# flasher.net
KiCad netlist of a schematic drawn in EAGLE
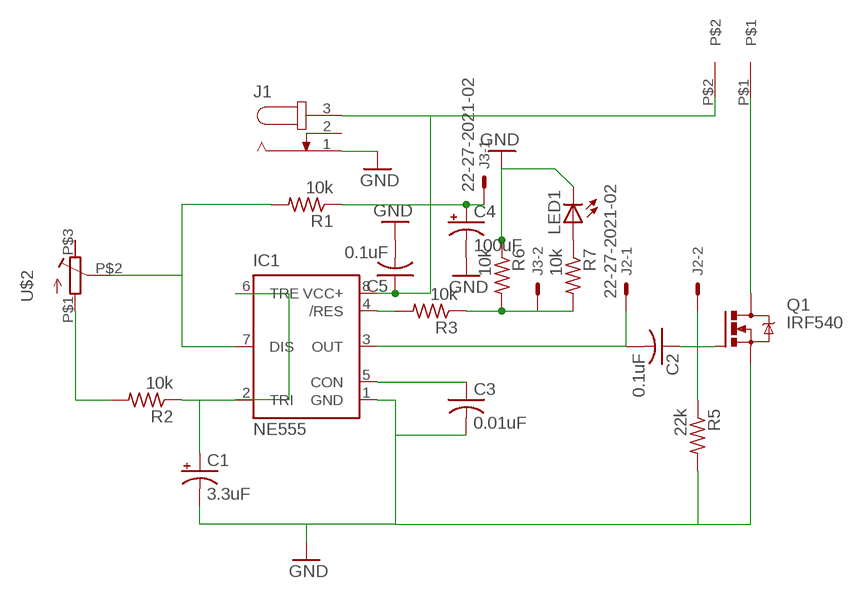
[diagram p0: schematic, sheet 1]

(export (version "E")
  (design (tool "Eeschema 10.0.6"))
  (components
    (comp (ref "C1")
      (value "3.3uF")
      (footprint "eagle-import:E2,5-5")
      (libsource (lib "eagle-import") (part "CPOL-USE2.5-5"))
    )
    (comp (ref "C2")
      (value "0.1uF")
      (footprint "eagle-import:C050-030X075")
      (libsource (lib "eagle-import") (part "C-US050-030X075"))
    )
    (comp (ref "C3")
      (value "0.01uF")
      (footprint "eagle-import:C025-025X050")
      (libsource (lib "eagle-import") (part "C-US025-025X050"))
    )
    (comp (ref "C4")
      (value "100uF")
      (footprint "eagle-import:E2,5-5")
      (libsource (lib "eagle-import") (part "CPOL-USE2.5-5"))
    )
    (comp (ref "C5")
      (value "0.1uF")
      (footprint "eagle-import:C025-025X050")
      (libsource (lib "eagle-import") (part "C-US025-025X050"))
    )
    (comp (ref "IC1")
      (value "NE555")
      (footprint "eagle-import:DIL-08")
      (fields (field (name "MF") "Arrow Electronics") (field (name "MPN") "NE555N"))
      (libsource (lib "eagle-import") (part "NE555"))
    )
    (comp (ref "J1")
      (value "JACK-PLUG0")
      (footprint "eagle-import:SPC4077")
      (libsource (lib "eagle-import") (part "JACK-PLUG0"))
    )
    (comp (ref "J2")
      (value "22-27-2021-02")
      (footprint "eagle-import:6410-02")
      (libsource (lib "eagle-import") (part "22-?-0227-2021"))
    )
    (comp (ref "J3")
      (value "22-27-2021-02")
      (footprint "eagle-import:6410-02")
      (libsource (lib "eagle-import") (part "22-?-0227-2021"))
    )
    (comp (ref "LED1")
      (value "LED5MM")
      (footprint "eagle-import:LED5MM")
      (libsource (lib "eagle-import") (part "LED5MM"))
    )
    (comp (ref "Q1")
      (value "IRF540")
      (footprint "eagle-import:TO220BV")
      (libsource (lib "eagle-import") (part "IRF540"))
    )
    (comp (ref "R1")
      (value "10k")
      (footprint "eagle-import:0207_10")
      (libsource (lib "eagle-import") (part "R-US_0207/10"))
    )
    (comp (ref "R2")
      (value "10k")
      (footprint "eagle-import:0207_10")
      (libsource (lib "eagle-import") (part "R-US_0207/10"))
    )
    (comp (ref "R3")
      (value "10k")
      (footprint "eagle-import:0207_10")
      (libsource (lib "eagle-import") (part "R-US_0207/10"))
    )
    (comp (ref "R5")
      (value "22k")
      (footprint "eagle-import:0207_10")
      (libsource (lib "eagle-import") (part "R-US_0207/10"))
    )
    (comp (ref "R6")
      (value "10k")
      (footprint "eagle-import:0207_10")
      (libsource (lib "eagle-import") (part "R-US_0207/10"))
    )
    (comp (ref "R7")
      (value "10k")
      (footprint "eagle-import:0207_10")
      (libsource (lib "eagle-import") (part "R-US_0207/10"))
    )
    (comp (ref "U$1")
      (value "DG301-5.0")
      (footprint "eagle-import:DG301-5.0")
      (libsource (lib "eagle-import") (part "DG301-5.0"))
    )
    (comp (ref "U$2")
      (value "PANELMOUNT_POT")
      (footprint "eagle-import:PANELMOUNT_POT")
      (libsource (lib "eagle-import") (part "PANELMOUNT_POT"))
    )
  )
  (nets
    (net (code "1") (name "GND") (class "Default")
      (node (ref "C1") (pin "-") (pinfunction "-_-") (pintype "passive"))
      (node (ref "C3") (pin "2") (pinfunction "2_2") (pintype "passive"))
      (node (ref "C4") (pin "-") (pinfunction "-_-") (pintype "passive"))
      (node (ref "C5") (pin "2") (pinfunction "2_2") (pintype "passive"))
      (node (ref "IC1") (pin "1") (pinfunction "GND_1") (pintype "power_in"))
      (node (ref "J1") (pin "1") (pinfunction "1_1") (pintype "passive"))
      (node (ref "LED1") (pin "K") (pinfunction "C_K") (pintype "passive"))
      (node (ref "Q1") (pin "S") (pinfunction "S_S") (pintype "passive"))
      (node (ref "R5") (pin "2") (pinfunction "2_2") (pintype "passive"))
      (node (ref "R6") (pin "1") (pinfunction "1_1") (pintype "passive"))
    )
    (net (code "2") (name "Net-(IC1-CON)") (class "Default")
      (node (ref "C3") (pin "1") (pinfunction "1_1") (pintype "passive"))
      (node (ref "IC1") (pin "5") (pinfunction "CON_5") (pintype "input"))
    )
    (net (code "3") (name "Net-(IC1-DIS)") (class "Default")
      (node (ref "IC1") (pin "7") (pinfunction "DIS_7") (pintype "input"))
      (node (ref "R1") (pin "2") (pinfunction "2_2") (pintype "passive"))
      (node (ref "U$2") (pin "P$2") (pinfunction "2_P$2") (pintype "passive"))
    )
    (net (code "4") (name "Net-(IC1-OUT)") (class "Default")
      (node (ref "C2") (pin "2") (pinfunction "2_2") (pintype "passive"))
      (node (ref "IC1") (pin "3") (pinfunction "OUT_3") (pintype "output"))
      (node (ref "J2") (pin "1") (pinfunction "S_1") (pintype "passive"))
    )
    (net (code "5") (name "Net-(IC1-TRE)") (class "Default")
      (node (ref "C1") (pin "+") (pinfunction "+_+") (pintype "passive"))
      (node (ref "IC1") (pin "2") (pinfunction "TRI_2") (pintype "input"))
      (node (ref "IC1") (pin "6") (pinfunction "TRE_6") (pintype "input"))
      (node (ref "R2") (pin "1") (pinfunction "1_1") (pintype "passive"))
    )
    (net (code "6") (name "Net-(IC1-VCC+)") (class "Default")
      (node (ref "C4") (pin "+") (pinfunction "+_+") (pintype "passive"))
      (node (ref "C5") (pin "1") (pinfunction "1_1") (pintype "passive"))
      (node (ref "IC1") (pin "8") (pinfunction "VCC+_8") (pintype "power_in"))
      (node (ref "J1") (pin "3") (pinfunction "3_3") (pintype "passive"))
      (node (ref "J3") (pin "1") (pinfunction "S_1") (pintype "passive"))
      (node (ref "R1") (pin "1") (pinfunction "1_1") (pintype "passive"))
      (node (ref "U$1") (pin "P$2") (pinfunction "P$2_P$2") (pintype "bidirectional"))
    )
    (net (code "7") (name "Net-(IC1-{slash}RES)") (class "Default")
      (node (ref "IC1") (pin "4") (pinfunction "/RES_4") (pintype "input"))
      (node (ref "R3") (pin "2") (pinfunction "2_2") (pintype "passive"))
    )
    (net (code "8") (name "Net-(J2B-S)") (class "Default")
      (node (ref "C2") (pin "1") (pinfunction "1_1") (pintype "passive"))
      (node (ref "J2") (pin "2") (pinfunction "S_2") (pintype "passive"))
      (node (ref "Q1") (pin "G") (pinfunction "G_G") (pintype "passive"))
      (node (ref "R5") (pin "1") (pinfunction "1_1") (pintype "passive"))
    )
    (net (code "9") (name "Net-(J3B-S)") (class "Default")
      (node (ref "J3") (pin "2") (pinfunction "S_2") (pintype "passive"))
      (node (ref "R3") (pin "1") (pinfunction "1_1") (pintype "passive"))
      (node (ref "R6") (pin "2") (pinfunction "2_2") (pintype "passive"))
      (node (ref "R7") (pin "2") (pinfunction "2_2") (pintype "passive"))
    )
    (net (code "10") (name "Net-(LED1-PadA)") (class "Default")
      (node (ref "LED1") (pin "A") (pinfunction "A_A") (pintype "passive"))
      (node (ref "R7") (pin "1") (pinfunction "1_1") (pintype "passive"))
    )
    (net (code "11") (name "Net-(Q1-PadD)") (class "Default")
      (node (ref "Q1") (pin "D") (pinfunction "D_D") (pintype "passive"))
      (node (ref "U$1") (pin "P$1") (pinfunction "P$1_P$1") (pintype "bidirectional"))
    )
    (net (code "12") (name "Net-(U$2-1)") (class "Default")
      (node (ref "R2") (pin "2") (pinfunction "2_2") (pintype "passive"))
      (node (ref "U$2") (pin "P$1") (pinfunction "1_P$1") (pintype "passive"))
    )
    (net (code "13") (name "unconnected-(J1-Pad2)") (class "Default")
      (node (ref "J1") (pin "2") (pinfunction "2_2") (pintype "passive"))
    )
    (net (code "14") (name "unconnected-(U$2-3-PadP$3)") (class "Default")
      (node (ref "U$2") (pin "P$3") (pinfunction "3_P$3") (pintype "passive"))
    )
  )
)
